# Bats-n-Gons.net
KiCad netlist of a schematic drawn in EAGLE
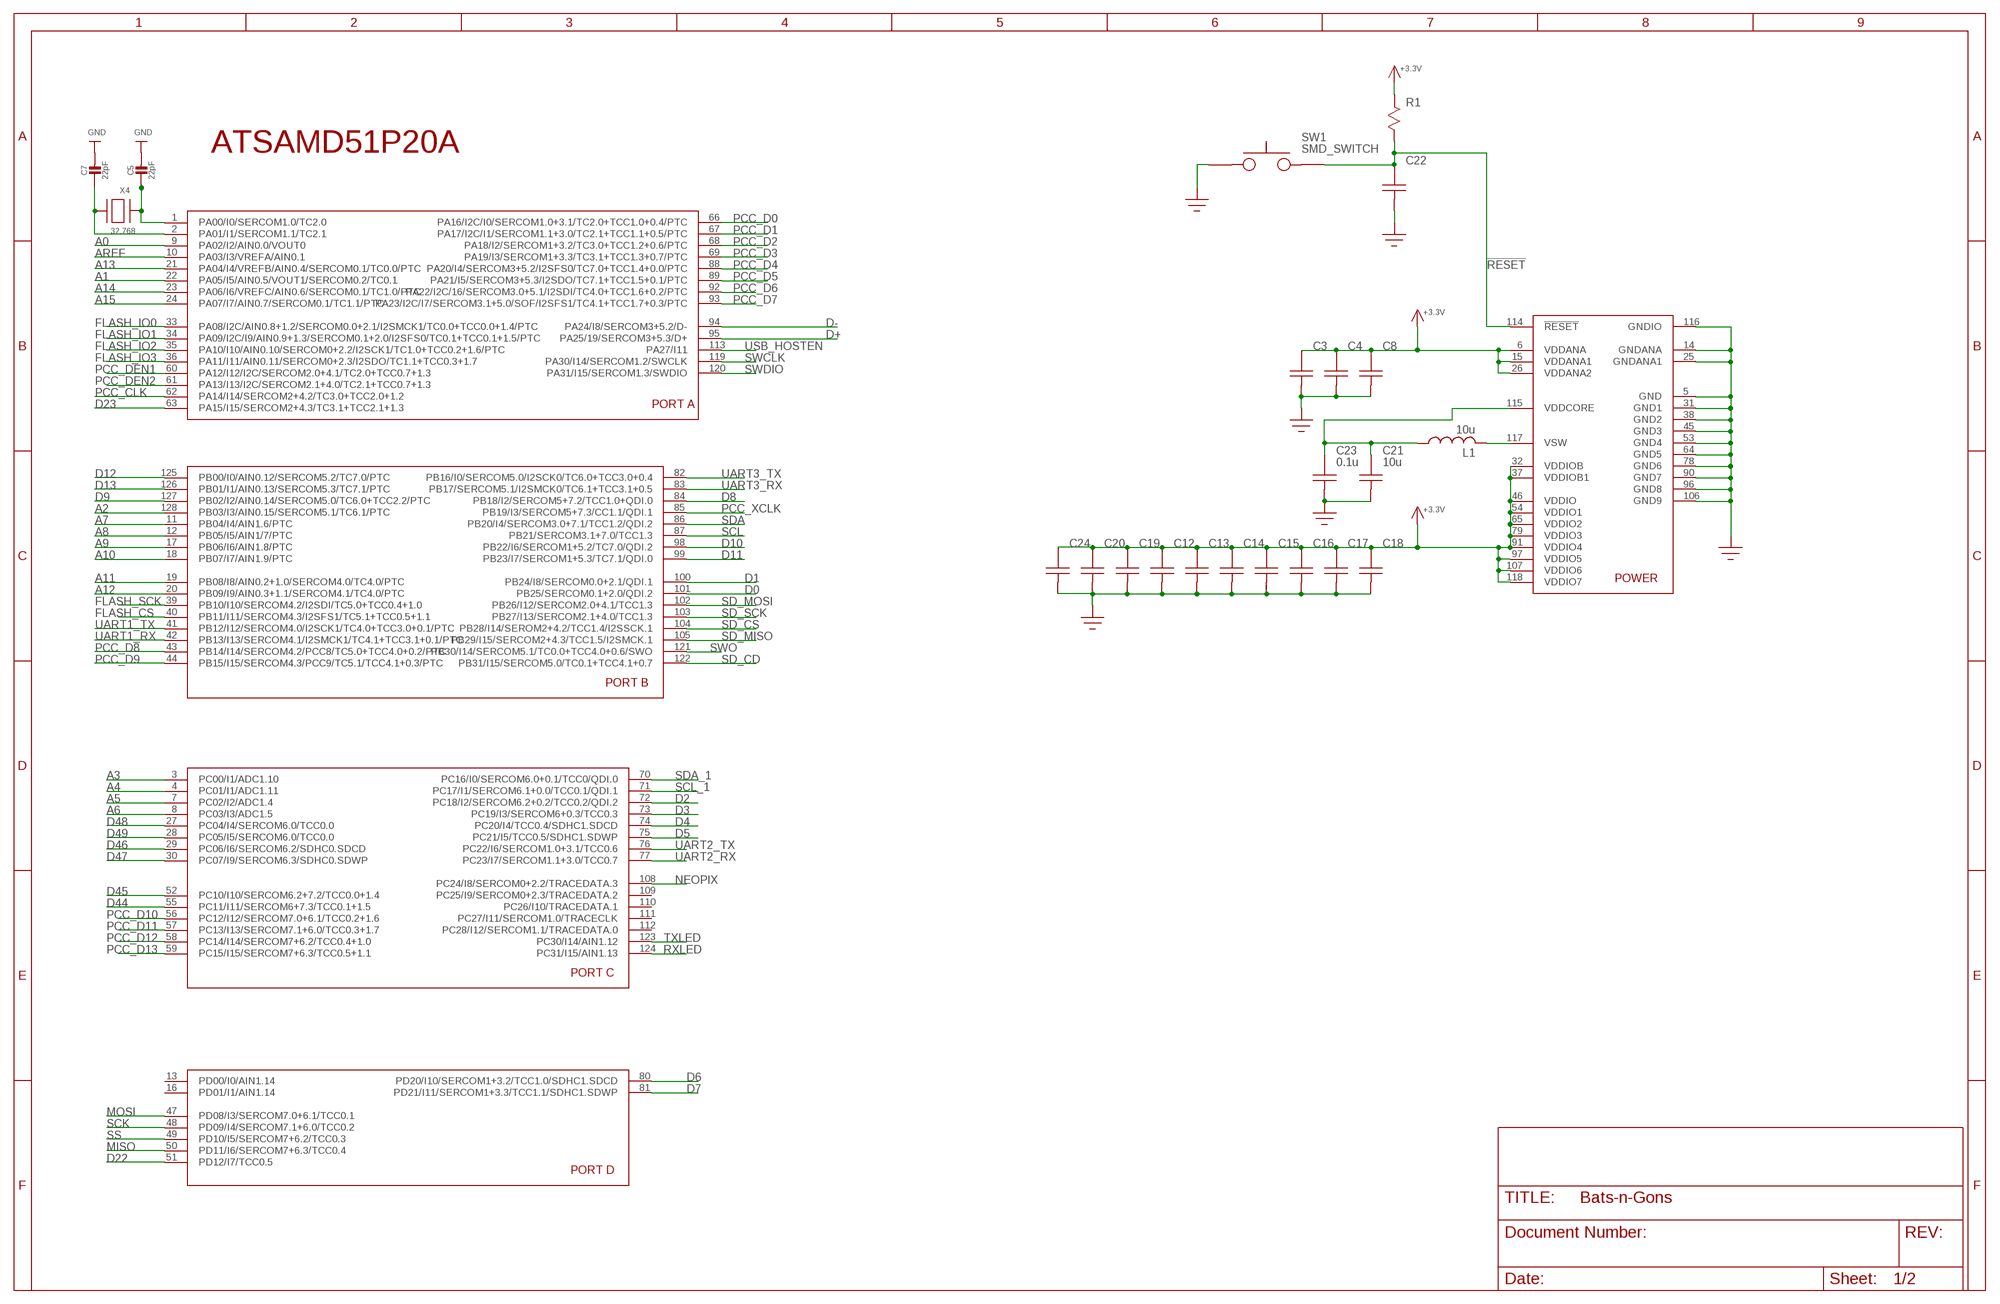
[diagram p0: schematic, sheet 1]
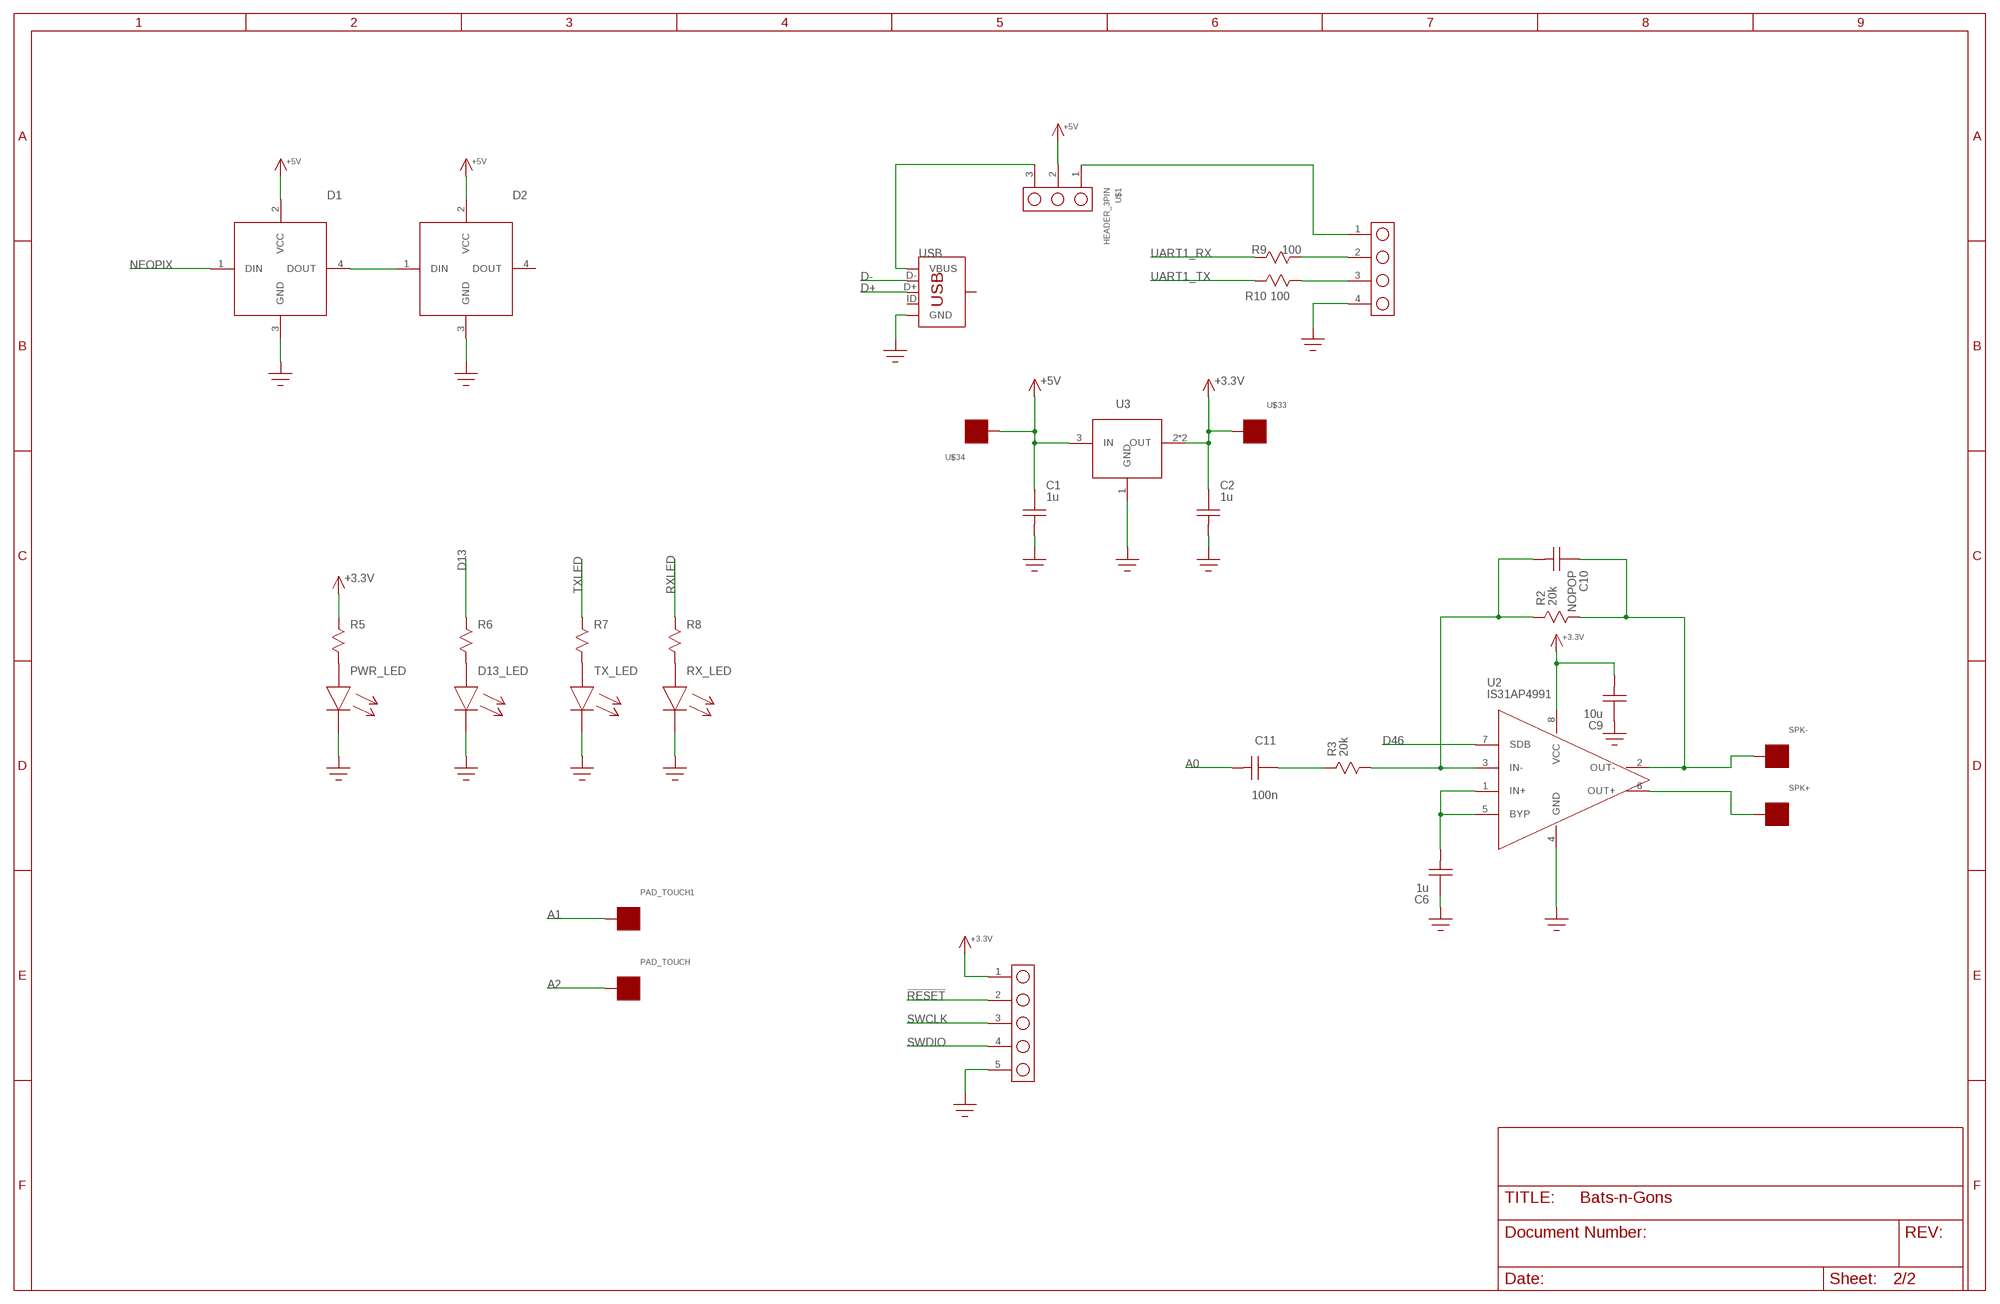
[diagram p1: schematic, sheet 2]

(export (version "E")
  (design (tool "Eeschema 10.0.6"))
  (components
    (comp (ref "C3")
      (value "C0603")
      (footprint "eagle-import:C0603")
      (libsource (lib "eagle-import") (part "C0603"))
    )
    (comp (ref "C4")
      (value "C0603")
      (footprint "eagle-import:C0603")
      (libsource (lib "eagle-import") (part "C0603"))
    )
    (comp (ref "C5")
      (value "22pF")
      (footprint "eagle-import:0603-NO")
      (libsource (lib "eagle-import") (part "CAP_CERAMIC0603_NO"))
    )
    (comp (ref "C7")
      (value "22pF")
      (footprint "eagle-import:0603-NO")
      (libsource (lib "eagle-import") (part "CAP_CERAMIC0603_NO"))
    )
    (comp (ref "C8")
      (value "C0603")
      (footprint "eagle-import:C0603")
      (libsource (lib "eagle-import") (part "C0603"))
    )
    (comp (ref "C12")
      (value "C0603")
      (footprint "eagle-import:C0603")
      (libsource (lib "eagle-import") (part "C0603"))
    )
    (comp (ref "C13")
      (value "C0603")
      (footprint "eagle-import:C0603")
      (libsource (lib "eagle-import") (part "C0603"))
    )
    (comp (ref "C14")
      (value "C0603")
      (footprint "eagle-import:C0603")
      (libsource (lib "eagle-import") (part "C0603"))
    )
    (comp (ref "C15")
      (value "C0603")
      (footprint "eagle-import:C0603")
      (libsource (lib "eagle-import") (part "C0603"))
    )
    (comp (ref "C16")
      (value "C0603")
      (footprint "eagle-import:C0603")
      (libsource (lib "eagle-import") (part "C0603"))
    )
    (comp (ref "C17")
      (value "C0603")
      (footprint "eagle-import:C0603")
      (libsource (lib "eagle-import") (part "C0603"))
    )
    (comp (ref "C18")
      (value "C0603")
      (footprint "eagle-import:C0603")
      (libsource (lib "eagle-import") (part "C0603"))
    )
    (comp (ref "C19")
      (value "C0603")
      (footprint "eagle-import:C0603")
      (libsource (lib "eagle-import") (part "C0603"))
    )
    (comp (ref "C20")
      (value "C0603")
      (footprint "eagle-import:C0603")
      (libsource (lib "eagle-import") (part "C0603"))
    )
    (comp (ref "C21")
      (value "10u")
      (footprint "eagle-import:C0603")
      (libsource (lib "eagle-import") (part "C0603"))
    )
    (comp (ref "C22")
      (value "C0603")
      (footprint "eagle-import:C0603")
      (libsource (lib "eagle-import") (part "C0603"))
    )
    (comp (ref "C23")
      (value "0.1u")
      (footprint "eagle-import:C0603")
      (libsource (lib "eagle-import") (part "C0603"))
    )
    (comp (ref "C24")
      (value "C0603")
      (footprint "eagle-import:C0603")
      (libsource (lib "eagle-import") (part "C0603"))
    )
    (comp (ref "L1")
      (value "10u")
      (footprint "eagle-import:L24X24")
      (libsource (lib "eagle-import") (part "INDUCTOR2424"))
    )
    (comp (ref "R1")
      (value "R0603")
      (footprint "eagle-import:R0603")
      (libsource (lib "eagle-import") (part "R0603"))
    )
    (comp (ref "SW1")
      (value "SMD_SWITCH")
      (footprint "eagle-import:SMD_SWITCH")
      (libsource (lib "eagle-import") (part "SMD_SWITCH"))
    )
    (comp (ref "U1")
      (value "SAMD51PXXA")
      (footprint "eagle-import:SQFP-S-14X14-128")
      (libsource (lib "eagle-import") (part "SAMD51PXXA"))
    )
    (comp (ref "X4")
      (value "32.768")
      (footprint "eagle-import:XTAL3215")
      (libsource (lib "eagle-import") (part "XTAL-3.2X1.5"))
    )
    (comp (ref "C1")
      (value "1u")
      (footprint "eagle-import:C0603")
      (libsource (lib "eagle-import") (part "yapo_C0603"))
    )
    (comp (ref "C2")
      (value "1u")
      (footprint "eagle-import:C0603")
      (libsource (lib "eagle-import") (part "yapo_C0603"))
    )
    (comp (ref "C6")
      (value "1u")
      (footprint "eagle-import:C0603")
      (libsource (lib "eagle-import") (part "C0603"))
    )
    (comp (ref "C9")
      (value "10u")
      (footprint "eagle-import:1206")
      (libsource (lib "eagle-import") (part "C1206"))
    )
    (comp (ref "C10")
      (value "NOPOP")
      (footprint "eagle-import:C0603")
      (libsource (lib "eagle-import") (part "C0603"))
    )
    (comp (ref "C11")
      (value "100n")
      (footprint "eagle-import:C0603")
      (libsource (lib "eagle-import") (part "C0603"))
    )
    (comp (ref "D1")
      (value "NEOPIXEL")
      (footprint "eagle-import:LED-RGB-THRU")
      (libsource (lib "eagle-import") (part "NEOPIXEL"))
    )
    (comp (ref "D2")
      (value "NEOPIXEL")
      (footprint "eagle-import:LED-RGB-THRU")
      (libsource (lib "eagle-import") (part "NEOPIXEL"))
    )
    (comp (ref "D13_LED")
      (value "LED_0603")
      (footprint "eagle-import:LED_0603")
      (libsource (lib "eagle-import") (part "LED_0603"))
    )
    (comp (ref "J1")
      (value "HEADER_4PIN")
      (footprint "eagle-import:HEADER_4PIN")
      (libsource (lib "eagle-import") (part "HEADER_4PIN"))
    )
    (comp (ref "J2")
      (value "HEADER_5PIN")
      (footprint "eagle-import:HEADER_5PIN")
      (libsource (lib "eagle-import") (part "HEADER_5PIN"))
    )
    (comp (ref "PAD_TOUCH")
      (value "PAD")
      (footprint "eagle-import:PAD-ROUND-100MIL-MASK")
      (libsource (lib "eagle-import") (part "PAD"))
    )
    (comp (ref "PAD_TOUCH1")
      (value "PAD")
      (footprint "eagle-import:PAD-ROUND-100MIL-MASK")
      (libsource (lib "eagle-import") (part "PAD"))
    )
    (comp (ref "PWR_LED")
      (value "LED_0603")
      (footprint "eagle-import:LED_0603")
      (libsource (lib "eagle-import") (part "LED_0603"))
    )
    (comp (ref "R2")
      (value "20k")
      (footprint "eagle-import:R0603")
      (libsource (lib "eagle-import") (part "R0603"))
    )
    (comp (ref "R3")
      (value "20k")
      (footprint "eagle-import:R0603")
      (libsource (lib "eagle-import") (part "R0603"))
    )
    (comp (ref "R5")
      (value "R0603")
      (footprint "eagle-import:R0603")
      (libsource (lib "eagle-import") (part "R0603"))
    )
    (comp (ref "R6")
      (value "R0603")
      (footprint "eagle-import:R0603")
      (libsource (lib "eagle-import") (part "R0603"))
    )
    (comp (ref "R7")
      (value "R0603")
      (footprint "eagle-import:R0603")
      (libsource (lib "eagle-import") (part "R0603"))
    )
    (comp (ref "R8")
      (value "R0603")
      (footprint "eagle-import:R0603")
      (libsource (lib "eagle-import") (part "R0603"))
    )
    (comp (ref "R9")
      (value "100")
      (footprint "eagle-import:R0603")
      (libsource (lib "eagle-import") (part "R0603"))
    )
    (comp (ref "R10")
      (value "100")
      (footprint "eagle-import:R0603")
      (libsource (lib "eagle-import") (part "R0603"))
    )
    (comp (ref "RX_LED")
      (value "LED_0603")
      (footprint "eagle-import:LED_0603")
      (libsource (lib "eagle-import") (part "LED_0603"))
    )
    (comp (ref "SPK+")
      (value "PAD100MIL")
      (footprint "eagle-import:PAD_100MIL")
      (libsource (lib "eagle-import") (part "PAD100MIL"))
    )
    (comp (ref "SPK-")
      (value "PAD100MIL")
      (footprint "eagle-import:PAD_100MIL")
      (libsource (lib "eagle-import") (part "PAD100MIL"))
    )
    (comp (ref "TX_LED")
      (value "LED_0603")
      (footprint "eagle-import:LED_0603")
      (libsource (lib "eagle-import") (part "LED_0603"))
    )
    (comp (ref "U$1")
      (value "HEADER_3PIN")
      (footprint "eagle-import:HEADER_3PIN")
      (libsource (lib "eagle-import") (part "HEADER_3PIN"))
    )
    (comp (ref "U$33")
      (value "PADROUND-50MIL")
      (footprint "eagle-import:PAD-ROUND-50MIL")
      (libsource (lib "eagle-import") (part "PADROUND-50MIL"))
    )
    (comp (ref "U$34")
      (value "PADROUND-50MIL")
      (footprint "eagle-import:PAD-ROUND-50MIL")
      (libsource (lib "eagle-import") (part "PADROUND-50MIL"))
    )
    (comp (ref "U2")
      (value "IS31AP4991")
      (footprint "eagle-import:SOIC8")
      (libsource (lib "eagle-import") (part "IS31AP4991SOIC"))
    )
    (comp (ref "U3")
      (value "AZ1117E")
      (footprint "eagle-import:SOT-223")
      (libsource (lib "eagle-import") (part "AZ1117E"))
    )
    (comp (ref "USB")
      (value "USB_MICRO_LEGS")
      (footprint "eagle-import:USB_MICRO_LEGS_2")
      (libsource (lib "eagle-import") (part "USB_MICRO_LEGS"))
    )
  )
  (nets
    (net (code "1") (name "+3.3V") (class "Default")
      (node (ref "C12") (pin "P$2") (pinfunction "P$2_P$2") (pintype "bidirectional"))
      (node (ref "C13") (pin "P$2") (pinfunction "P$2_P$2") (pintype "bidirectional"))
      (node (ref "C14") (pin "P$2") (pinfunction "P$2_P$2") (pintype "bidirectional"))
      (node (ref "C15") (pin "P$2") (pinfunction "P$2_P$2") (pintype "bidirectional"))
      (node (ref "C16") (pin "P$2") (pinfunction "P$2_P$2") (pintype "bidirectional"))
      (node (ref "C17") (pin "P$2") (pinfunction "P$2_P$2") (pintype "bidirectional"))
      (node (ref "C18") (pin "P$2") (pinfunction "P$2_P$2") (pintype "bidirectional"))
      (node (ref "C19") (pin "P$2") (pinfunction "P$2_P$2") (pintype "bidirectional"))
      (node (ref "C2") (pin "P$2") (pinfunction "P$2_P$2") (pintype "bidirectional"))
      (node (ref "C20") (pin "P$2") (pinfunction "P$2_P$2") (pintype "bidirectional"))
      (node (ref "C24") (pin "P$2") (pinfunction "P$2_P$2") (pintype "bidirectional"))
      (node (ref "C3") (pin "P$2") (pinfunction "P$2_P$2") (pintype "bidirectional"))
      (node (ref "C4") (pin "P$2") (pinfunction "P$2_P$2") (pintype "bidirectional"))
      (node (ref "C8") (pin "P$2") (pinfunction "P$2_P$2") (pintype "bidirectional"))
      (node (ref "C9") (pin "P$1") (pinfunction "P$1_P$1") (pintype "bidirectional"))
      (node (ref "J2") (pin "1") (pinfunction "1_1") (pintype "bidirectional"))
      (node (ref "R1") (pin "P$1") (pinfunction "P$3_P$1") (pintype "bidirectional"))
      (node (ref "R5") (pin "P$1") (pinfunction "P$3_P$1") (pintype "bidirectional"))
      (node (ref "U$33") (pin "P$1") (pinfunction "P$1_P$1") (pintype "bidirectional"))
      (node (ref "U1") (pin "107") (pinfunction "VDDIO6_107") (pintype "bidirectional"))
      (node (ref "U1") (pin "118") (pinfunction "VDDIO7_118") (pintype "bidirectional"))
      (node (ref "U1") (pin "15") (pinfunction "VDDANA1_15") (pintype "bidirectional"))
      (node (ref "U1") (pin "26") (pinfunction "VDDANA2_26") (pintype "bidirectional"))
      (node (ref "U1") (pin "32") (pinfunction "VDDIOB_32") (pintype "bidirectional"))
      (node (ref "U1") (pin "37") (pinfunction "VDDIOB1_37") (pintype "bidirectional"))
      (node (ref "U1") (pin "46") (pinfunction "VDDIO_46") (pintype "bidirectional"))
      (node (ref "U1") (pin "54") (pinfunction "VDDIO1_54") (pintype "bidirectional"))
      (node (ref "U1") (pin "6") (pinfunction "VDDANA_6") (pintype "bidirectional"))
      (node (ref "U1") (pin "65") (pinfunction "VDDIO2_65") (pintype "bidirectional"))
      (node (ref "U1") (pin "79") (pinfunction "VDDIO3_79") (pintype "bidirectional"))
      (node (ref "U1") (pin "91") (pinfunction "VDDIO4_91") (pintype "bidirectional"))
      (node (ref "U1") (pin "97") (pinfunction "VDDIO5_97") (pintype "bidirectional"))
      (node (ref "U2") (pin "8") (pinfunction "VCC_8") (pintype "bidirectional"))
      (node (ref "U3") (pin "2") (pinfunction "OUT_2") (pintype "bidirectional"))
      (node (ref "U3") (pin "4") (pinfunction "OUT_4") (pintype "bidirectional"))
    )
    (net (code "2") (name "+5V") (class "Default")
      (node (ref "C1") (pin "P$2") (pinfunction "P$2_P$2") (pintype "bidirectional"))
      (node (ref "D1") (pin "2") (pinfunction "VCC_2") (pintype "bidirectional"))
      (node (ref "D2") (pin "2") (pinfunction "VCC_2") (pintype "bidirectional"))
      (node (ref "U$1") (pin "2") (pinfunction "2_2") (pintype "bidirectional"))
      (node (ref "U$34") (pin "P$1") (pinfunction "P$1_P$1") (pintype "bidirectional"))
      (node (ref "U3") (pin "3") (pinfunction "IN_3") (pintype "bidirectional"))
    )
    (net (code "3") (name "A0") (class "Default")
      (node (ref "C11") (pin "P$1") (pinfunction "P$1_P$1") (pintype "bidirectional"))
      (node (ref "U1") (pin "9") (pinfunction "PA02/I2/AIN0.0/VOUT0_9") (pintype "bidirectional"))
    )
    (net (code "4") (name "A1") (class "Default")
      (node (ref "PAD_TOUCH1") (pin "P$1") (pinfunction "P$1_P$1") (pintype "bidirectional"))
      (node (ref "U1") (pin "22") (pinfunction "PA05/I5/AIN0.5/VOUT1/SERCOM0.2/TC0.1_22") (pintype "bidirectional"))
    )
    (net (code "5") (name "A2") (class "Default")
      (node (ref "PAD_TOUCH") (pin "P$1") (pinfunction "P$1_P$1") (pintype "bidirectional"))
      (node (ref "U1") (pin "128") (pinfunction "PB03/I3/AIN0.15/SERCOM5.1/TC6.1/PTC_128") (pintype "bidirectional"))
    )
    (net (code "6") (name "A3") (class "Default")
      (node (ref "U1") (pin "3") (pinfunction "PC00/I1/ADC1.10_3") (pintype "bidirectional"))
    )
    (net (code "7") (name "A4") (class "Default")
      (node (ref "U1") (pin "4") (pinfunction "PC01/I1/ADC1.11_4") (pintype "bidirectional"))
    )
    (net (code "8") (name "A5") (class "Default")
      (node (ref "U1") (pin "7") (pinfunction "PC02/I2/ADC1.4_7") (pintype "bidirectional"))
    )
    (net (code "9") (name "A6") (class "Default")
      (node (ref "U1") (pin "8") (pinfunction "PC03/I3/ADC1.5_8") (pintype "bidirectional"))
    )
    (net (code "10") (name "A7") (class "Default")
      (node (ref "U1") (pin "11") (pinfunction "PB04/I4/AIN1.6/PTC_11") (pintype "bidirectional"))
    )
    (net (code "11") (name "A8") (class "Default")
      (node (ref "U1") (pin "12") (pinfunction "PB05/I5/AIN1/7/PTC_12") (pintype "bidirectional"))
    )
    (net (code "12") (name "A9") (class "Default")
      (node (ref "U1") (pin "17") (pinfunction "PB06/I6/AIN1.8/PTC_17") (pintype "bidirectional"))
    )
    (net (code "13") (name "A10") (class "Default")
      (node (ref "U1") (pin "18") (pinfunction "PB07/I7/AIN1.9/PTC_18") (pintype "bidirectional"))
    )
    (net (code "14") (name "A11") (class "Default")
      (node (ref "U1") (pin "19") (pinfunction "PB08/I8/AIN0.2+1.0/SERCOM4.0/TC4.0/PTC_19") (pintype "bidirectional"))
    )
    (net (code "15") (name "A12") (class "Default")
      (node (ref "U1") (pin "20") (pinfunction "PB09/I9/AIN0.3+1.1/SERCOM4.1/TC4.0/PTC_20") (pintype "bidirectional"))
    )
    (net (code "16") (name "A13") (class "Default")
      (node (ref "U1") (pin "21") (pinfunction "PA04/I4/VREFB/AIN0.4/SERCOM0.1/TC0.0/PTC_21") (pintype "bidirectional"))
    )
    (net (code "17") (name "A14") (class "Default")
      (node (ref "U1") (pin "23") (pinfunction "PA06/I6/VREFC/AIN0.6/SERCOM0.1/TC1.0/PTC_23") (pintype "bidirectional"))
    )
    (net (code "18") (name "A15") (class "Default")
      (node (ref "U1") (pin "24") (pinfunction "PA07/I7/AIN0.7/SERCOM0.1/TC1.1/PTC_24") (pintype "bidirectional"))
    )
    (net (code "19") (name "AREF") (class "Default")
      (node (ref "U1") (pin "10") (pinfunction "PA03/I3/VREFA/AIN0.1_10") (pintype "bidirectional"))
    )
    (net (code "20") (name "D+") (class "Default")
      (node (ref "U1") (pin "95") (pinfunction "PA25/19/SERCOM3+5.3/D+_95") (pintype "bidirectional"))
      (node (ref "USB") (pin "D+") (pinfunction "D+_D+") (pintype "bidirectional"))
    )
    (net (code "21") (name "D-") (class "Default")
      (node (ref "U1") (pin "94") (pinfunction "PA24/I8/SERCOM3+5.2/D-_94") (pintype "bidirectional"))
      (node (ref "USB") (pin "D-") (pinfunction "D-_D-") (pintype "bidirectional"))
    )
    (net (code "22") (name "D0") (class "Default")
      (node (ref "U1") (pin "101") (pinfunction "PB25/SERCOM0.1+2.0/QDI.2_101") (pintype "bidirectional"))
    )
    (net (code "23") (name "D1") (class "Default")
      (node (ref "U1") (pin "100") (pinfunction "PB24/I8/SERCOM0.0+2.1/QDI.1_100") (pintype "bidirectional"))
    )
    (net (code "24") (name "D2") (class "Default")
      (node (ref "U1") (pin "72") (pinfunction "PC18/I2/SERCOM6.2+0.2/TCC0.2/QDI.2_72") (pintype "bidirectional"))
    )
    (net (code "25") (name "D3") (class "Default")
      (node (ref "U1") (pin "73") (pinfunction "PC19/I3/SERCOM6+0.3/TCC0.3_73") (pintype "bidirectional"))
    )
    (net (code "26") (name "D4") (class "Default")
      (node (ref "U1") (pin "74") (pinfunction "PC20/I4/TCC0.4/SDHC1.SDCD_74") (pintype "bidirectional"))
    )
    (net (code "27") (name "D5") (class "Default")
      (node (ref "U1") (pin "75") (pinfunction "PC21/I5/TCC0.5/SDHC1.SDWP_75") (pintype "bidirectional"))
    )
    (net (code "28") (name "D6") (class "Default")
      (node (ref "U1") (pin "80") (pinfunction "PD20/I10/SERCOM1+3.2/TCC1.0/SDHC1.SDCD_80") (pintype "bidirectional"))
    )
    (net (code "29") (name "D7") (class "Default")
      (node (ref "U1") (pin "81") (pinfunction "PD21/I11/SERCOM1+3.3/TCC1.1/SDHC1.SDWP_81") (pintype "bidirectional"))
    )
    (net (code "30") (name "D8") (class "Default")
      (node (ref "U1") (pin "84") (pinfunction "PB18/I2/SERCOM5+7.2/TCC1.0+QDI.0_84") (pintype "bidirectional"))
    )
    (net (code "31") (name "D9") (class "Default")
      (node (ref "U1") (pin "127") (pinfunction "PB02/I2/AIN0.14/SERCOM5.0/TC6.0+TCC2.2/PTC_127") (pintype "bidirectional"))
    )
    (net (code "32") (name "D10") (class "Default")
      (node (ref "U1") (pin "98") (pinfunction "PB22/I6/SERCOM1+5.2/TC7.0/QDI.2_98") (pintype "bidirectional"))
    )
    (net (code "33") (name "D11") (class "Default")
      (node (ref "U1") (pin "99") (pinfunction "PB23/I7/SERCOM1+5.3/TC7.1/QDI.0_99") (pintype "bidirectional"))
    )
    (net (code "34") (name "D12") (class "Default")
      (node (ref "U1") (pin "125") (pinfunction "PB00/I0/AIN0.12/SERCOM5.2/TC7.0/PTC_125") (pintype "bidirectional"))
    )
    (net (code "35") (name "D13") (class "Default")
      (node (ref "R6") (pin "P$1") (pinfunction "P$3_P$1") (pintype "bidirectional"))
      (node (ref "U1") (pin "126") (pinfunction "PB01/I1/AIN0.13/SERCOM5.3/TC7.1/PTC_126") (pintype "bidirectional"))
    )
    (net (code "36") (name "D22") (class "Default")
      (node (ref "U1") (pin "51") (pinfunction "PD12/I7/TCC0.5_51") (pintype "bidirectional"))
    )
    (net (code "37") (name "D23") (class "Default")
      (node (ref "U1") (pin "63") (pinfunction "PA15/I15/SERCOM2+4.3/TC3.1+TCC2.1+1.3_63") (pintype "bidirectional"))
    )
    (net (code "38") (name "D44") (class "Default")
      (node (ref "U1") (pin "55") (pinfunction "PC11/I11/SERCOM6+7.3/TCC0.1+1.5_55") (pintype "bidirectional"))
    )
    (net (code "39") (name "D45") (class "Default")
      (node (ref "U1") (pin "52") (pinfunction "PC10/I10/SERCOM6.2+7.2/TCC0.0+1.4_52") (pintype "bidirectional"))
    )
    (net (code "40") (name "D46") (class "Default")
      (node (ref "U1") (pin "29") (pinfunction "PC06/I6/SERCOM6.2/SDHC0.SDCD_29") (pintype "bidirectional"))
      (node (ref "U2") (pin "7") (pinfunction "SDB_7") (pintype "bidirectional"))
    )
    (net (code "41") (name "D47") (class "Default")
      (node (ref "U1") (pin "30") (pinfunction "PC07/I9/SERCOM6.3/SDHC0.SDWP_30") (pintype "bidirectional"))
    )
    (net (code "42") (name "D48") (class "Default")
      (node (ref "U1") (pin "27") (pinfunction "PC04/I4/SERCOM6.0/TCC0.0_27") (pintype "bidirectional"))
    )
    (net (code "43") (name "D49") (class "Default")
      (node (ref "U1") (pin "28") (pinfunction "PC05/I5/SERCOM6.0/TCC0.0_28") (pintype "bidirectional"))
    )
    (net (code "44") (name "FLASH_CS") (class "Default")
      (node (ref "U1") (pin "40") (pinfunction "PB11/I11/SERCOM4.3/I2SFS1/TC5.1+TCC0.5+1.1_40") (pintype "bidirectional"))
    )
    (net (code "45") (name "FLASH_IO0") (class "Default")
      (node (ref "U1") (pin "33") (pinfunction "PA08/I2C/AIN0.8+1.2/SERCOM0.0+2.1/I2SMCK1/TC0.0+TCC0.0+1.4/PTC_33") (pintype "bidirectional"))
    )
    (net (code "46") (name "FLASH_IO1") (class "Default")
      (node (ref "U1") (pin "34") (pinfunction "PA09/I2C/I9/AIN0.9+1.3/SERCOM0.1+2.0/I2SFS0/TC0.1+TCC0.1+1.5/PTC_34") (pintype "bidirectional"))
    )
    (net (code "47") (name "FLASH_IO2") (class "Default")
      (node (ref "U1") (pin "35") (pinfunction "PA10/I10/AIN0.10/SERCOM0+2.2/I2SCK1/TC1.0+TCC0.2+1.6/PTC_35") (pintype "bidirectional"))
    )
    (net (code "48") (name "FLASH_IO3") (class "Default")
      (node (ref "U1") (pin "36") (pinfunction "PA11/I11/AIN0.11/SERCOM0+2.3/I2SDO/TC1.1+TCC0.3+1.7_36") (pintype "bidirectional"))
    )
    (net (code "49") (name "FLASH_SCK") (class "Default")
      (node (ref "U1") (pin "39") (pinfunction "PB10/I10/SERCOM4.2/I2SDI/TC5.0+TCC0.4+1.0_39") (pintype "bidirectional"))
    )
    (net (code "50") (name "GND") (class "Default")
      (node (ref "C1") (pin "P$1") (pinfunction "P$1_P$1") (pintype "bidirectional"))
      (node (ref "C12") (pin "P$1") (pinfunction "P$1_P$1") (pintype "bidirectional"))
      (node (ref "C13") (pin "P$1") (pinfunction "P$1_P$1") (pintype "bidirectional"))
      (node (ref "C14") (pin "P$1") (pinfunction "P$1_P$1") (pintype "bidirectional"))
      (node (ref "C15") (pin "P$1") (pinfunction "P$1_P$1") (pintype "bidirectional"))
      (node (ref "C16") (pin "P$1") (pinfunction "P$1_P$1") (pintype "bidirectional"))
      (node (ref "C17") (pin "P$1") (pinfunction "P$1_P$1") (pintype "bidirectional"))
      (node (ref "C18") (pin "P$1") (pinfunction "P$1_P$1") (pintype "bidirectional"))
      (node (ref "C19") (pin "P$1") (pinfunction "P$1_P$1") (pintype "bidirectional"))
      (node (ref "C2") (pin "P$1") (pinfunction "P$1_P$1") (pintype "bidirectional"))
      (node (ref "C20") (pin "P$1") (pinfunction "P$1_P$1") (pintype "bidirectional"))
      (node (ref "C21") (pin "P$1") (pinfunction "P$1_P$1") (pintype "bidirectional"))
      (node (ref "C22") (pin "P$1") (pinfunction "P$1_P$1") (pintype "bidirectional"))
      (node (ref "C23") (pin "P$1") (pinfunction "P$1_P$1") (pintype "bidirectional"))
      (node (ref "C24") (pin "P$1") (pinfunction "P$1_P$1") (pintype "bidirectional"))
      (node (ref "C3") (pin "P$1") (pinfunction "P$1_P$1") (pintype "bidirectional"))
      (node (ref "C4") (pin "P$1") (pinfunction "P$1_P$1") (pintype "bidirectional"))
      (node (ref "C5") (pin "2") (pinfunction "2_2") (pintype "passive"))
      (node (ref "C6") (pin "P$2") (pinfunction "P$2_P$2") (pintype "bidirectional"))
      (node (ref "C7") (pin "2") (pinfunction "2_2") (pintype "passive"))
      (node (ref "C8") (pin "P$1") (pinfunction "P$1_P$1") (pintype "bidirectional"))
      (node (ref "C9") (pin "P$2") (pinfunction "P$2_P$2") (pintype "bidirectional"))
      (node (ref "D1") (pin "3") (pinfunction "GND_3") (pintype "bidirectional"))
      (node (ref "D13_LED") (pin "C") (pinfunction "C_C") (pintype "bidirectional"))
      (node (ref "D2") (pin "3") (pinfunction "GND_3") (pintype "bidirectional"))
      (node (ref "J1") (pin "4") (pinfunction "4_4") (pintype "bidirectional"))
      (node (ref "J2") (pin "5") (pinfunction "5_5") (pintype "bidirectional"))
      (node (ref "PWR_LED") (pin "C") (pinfunction "C_C") (pintype "bidirectional"))
      (node (ref "RX_LED") (pin "C") (pinfunction "C_C") (pintype "bidirectional"))
      (node (ref "SW1") (pin "P$1") (pinfunction "P$1_P$1") (pintype "bidirectional"))
      (node (ref "SW1") (pin "P$2") (pinfunction "P$1_P$2") (pintype "bidirectional"))
      (node (ref "TX_LED") (pin "C") (pinfunction "C_C") (pintype "bidirectional"))
      (node (ref "U1") (pin "106") (pinfunction "GND9_106") (pintype "bidirectional"))
      (node (ref "U1") (pin "116") (pinfunction "GNDIO_116") (pintype "bidirectional"))
      (node (ref "U1") (pin "14") (pinfunction "GNDANA_14") (pintype "bidirectional"))
      (node (ref "U1") (pin "25") (pinfunction "GNDANA1_25") (pintype "bidirectional"))
      (node (ref "U1") (pin "31") (pinfunction "GND1_31") (pintype "bidirectional"))
      (node (ref "U1") (pin "38") (pinfunction "GND2_38") (pintype "bidirectional"))
      (node (ref "U1") (pin "45") (pinfunction "GND3_45") (pintype "bidirectional"))
      (node (ref "U1") (pin "5") (pinfunction "GND_5") (pintype "bidirectional"))
      (node (ref "U1") (pin "53") (pinfunction "GND4_53") (pintype "bidirectional"))
      (node (ref "U1") (pin "64") (pinfunction "GND5_64") (pintype "bidirectional"))
      (node (ref "U1") (pin "78") (pinfunction "GND6_78") (pintype "bidirectional"))
      (node (ref "U1") (pin "90") (pinfunction "GND7_90") (pintype "bidirectional"))
      (node (ref "U1") (pin "96") (pinfunction "GND8_96") (pintype "bidirectional"))
      (node (ref "U2") (pin "4") (pinfunction "GND_4") (pintype "bidirectional"))
      (node (ref "U3") (pin "1") (pinfunction "GND_1") (pintype "bidirectional"))
      (node (ref "USB") (pin "GND") (pinfunction "GND_GND") (pintype "power_in"))
    )
    (net (code "51") (name "MISO") (class "Default")
      (node (ref "U1") (pin "50") (pinfunction "PD11/I6/SERCOM7+6.3/TCC0.4_50") (pintype "bidirectional"))
    )
    (net (code "52") (name "MOSI") (class "Default")
      (node (ref "U1") (pin "47") (pinfunction "PD08/I3/SERCOM7.0+6.1/TCC0.1_47") (pintype "bidirectional"))
    )
    (net (code "53") (name "NEOPIX") (class "Default")
      (node (ref "D1") (pin "1") (pinfunction "DIN_1") (pintype "bidirectional"))
      (node (ref "U1") (pin "108") (pinfunction "PC24/I8/SERCOM0+2.2/TRACEDATA.3_108") (pintype "bidirectional"))
    )
    (net (code "54") (name "Net-(D1-DOUT)") (class "Default")
      (node (ref "D1") (pin "4") (pinfunction "DOUT_4") (pintype "bidirectional"))
      (node (ref "D2") (pin "1") (pinfunction "DIN_1") (pintype "bidirectional"))
    )
    (net (code "55") (name "Net-(J1-Pad1)") (class "Default")
      (node (ref "J1") (pin "1") (pinfunction "1_1") (pintype "bidirectional"))
      (node (ref "U$1") (pin "1") (pinfunction "1_1") (pintype "bidirectional"))
    )
    (net (code "56") (name "Net-(R2-P$3)") (class "Default")
      (node (ref "C10") (pin "P$1") (pinfunction "P$1_P$1") (pintype "bidirectional"))
      (node (ref "R2") (pin "P$1") (pinfunction "P$3_P$1") (pintype "bidirectional"))
      (node (ref "R3") (pin "P$2") (pinfunction "P$4_P$2") (pintype "bidirectional"))
      (node (ref "U2") (pin "3") (pinfunction "IN-_3") (pintype "bidirectional"))
    )
    (net (code "57") (name "Net-(R2-P$4)") (class "Default")
      (node (ref "C10") (pin "P$2") (pinfunction "P$2_P$2") (pintype "bidirectional"))
      (node (ref "R2") (pin "P$2") (pinfunction "P$4_P$2") (pintype "bidirectional"))
      (node (ref "SPK-") (pin "P$1") (pinfunction "P$1_P$1") (pintype "bidirectional"))
      (node (ref "U2") (pin "2") (pinfunction "OUT-_2") (pintype "bidirectional"))
    )
    (net (code "58") (name "Net-(R3-P$3)") (class "Default")
      (node (ref "C11") (pin "P$2") (pinfunction "P$2_P$2") (pintype "bidirectional"))
      (node (ref "R3") (pin "P$1") (pinfunction "P$3_P$1") (pintype "bidirectional"))
    )
    (net (code "59") (name "Net-(R5-P$4)") (class "Default")
      (node (ref "PWR_LED") (pin "A") (pinfunction "A_A") (pintype "bidirectional"))
      (node (ref "R5") (pin "P$2") (pinfunction "P$4_P$2") (pintype "bidirectional"))
    )
    (net (code "60") (name "Net-(R6-P$4)") (class "Default")
      (node (ref "D13_LED") (pin "A") (pinfunction "A_A") (pintype "bidirectional"))
      (node (ref "R6") (pin "P$2") (pinfunction "P$4_P$2") (pintype "bidirectional"))
    )
    (net (code "61") (name "Net-(R7-P$4)") (class "Default")
      (node (ref "R7") (pin "P$2") (pinfunction "P$4_P$2") (pintype "bidirectional"))
      (node (ref "TX_LED") (pin "A") (pinfunction "A_A") (pintype "bidirectional"))
    )
    (net (code "62") (name "Net-(R8-P$4)") (class "Default")
      (node (ref "R8") (pin "P$2") (pinfunction "P$4_P$2") (pintype "bidirectional"))
      (node (ref "RX_LED") (pin "A") (pinfunction "A_A") (pintype "bidirectional"))
    )
    (net (code "63") (name "Net-(R9-P$4)") (class "Default")
      (node (ref "J1") (pin "2") (pinfunction "2_2") (pintype "bidirectional"))
      (node (ref "R9") (pin "P$2") (pinfunction "P$4_P$2") (pintype "bidirectional"))
    )
    (net (code "64") (name "Net-(R10-P$4)") (class "Default")
      (node (ref "J1") (pin "3") (pinfunction "3_3") (pintype "bidirectional"))
      (node (ref "R10") (pin "P$2") (pinfunction "P$4_P$2") (pintype "bidirectional"))
    )
    (net (code "65") (name "Net-(U$1-Pad3)") (class "Default")
      (node (ref "U$1") (pin "3") (pinfunction "3_3") (pintype "bidirectional"))
      (node (ref "USB") (pin "VBUS") (pinfunction "VBUS_VBUS") (pintype "power_in"))
    )
    (net (code "66") (name "Net-(U1A-PA00{slash}I0{slash}SERCOM1.0{slash}TC2.0)") (class "Default")
      (node (ref "C5") (pin "1") (pinfunction "1_1") (pintype "passive"))
      (node (ref "U1") (pin "1") (pinfunction "PA00/I0/SERCOM1.0/TC2.0_1") (pintype "bidirectional"))
      (node (ref "X4") (pin "P$1") (pinfunction "P$1_P$1") (pintype "bidirectional"))
    )
    (net (code "67") (name "Net-(U1A-PA01{slash}I1{slash}SERCOM1.1{slash}TC2.1)") (class "Default")
      (node (ref "C7") (pin "1") (pinfunction "1_1") (pintype "passive"))
      (node (ref "U1") (pin "2") (pinfunction "PA01/I1/SERCOM1.1/TC2.1_2") (pintype "bidirectional"))
      (node (ref "X4") (pin "P$2") (pinfunction "P$2_P$2") (pintype "bidirectional"))
    )
    (net (code "68") (name "Net-(U1E-VDDCORE)") (class "Default")
      (node (ref "C21") (pin "P$2") (pinfunction "P$2_P$2") (pintype "bidirectional"))
      (node (ref "C23") (pin "P$2") (pinfunction "P$2_P$2") (pintype "bidirectional"))
      (node (ref "L1") (pin "1") (pinfunction "1_1") (pintype "passive"))
      (node (ref "U1") (pin "115") (pinfunction "VDDCORE_115") (pintype "bidirectional"))
    )
    (net (code "69") (name "Net-(U1E-VSW)") (class "Default")
      (node (ref "L1") (pin "2") (pinfunction "2_2") (pintype "passive"))
      (node (ref "U1") (pin "117") (pinfunction "VSW_117") (pintype "bidirectional"))
    )
    (net (code "70") (name "Net-(U2-BYP)") (class "Default")
      (node (ref "C6") (pin "P$1") (pinfunction "P$1_P$1") (pintype "bidirectional"))
      (node (ref "U2") (pin "1") (pinfunction "IN+_1") (pintype "bidirectional"))
      (node (ref "U2") (pin "5") (pinfunction "BYP_5") (pintype "bidirectional"))
    )
    (net (code "71") (name "Net-(U2-OUT+)") (class "Default")
      (node (ref "SPK+") (pin "P$1") (pinfunction "P$1_P$1") (pintype "bidirectional"))
      (node (ref "U2") (pin "6") (pinfunction "OUT+_6") (pintype "bidirectional"))
    )
    (net (code "72") (name "PCC_CLK") (class "Default")
      (node (ref "U1") (pin "62") (pinfunction "PA14/I14/SERCOM2+4.2/TC3.0+TCC2.0+1.2_62") (pintype "bidirectional"))
    )
    (net (code "73") (name "PCC_D0") (class "Default")
      (node (ref "U1") (pin "66") (pinfunction "PA16/I2C/I0/SERCOM1.0+3.1/TC2.0+TCC1.0+0.4/PTC_66") (pintype "bidirectional"))
    )
    (net (code "74") (name "PCC_D1") (class "Default")
      (node (ref "U1") (pin "67") (pinfunction "PA17/I2C/I1/SERCOM1.1+3.0/TC2.1+TCC1.1+0.5/PTC_67") (pintype "bidirectional"))
    )
    (net (code "75") (name "PCC_D2") (class "Default")
      (node (ref "U1") (pin "68") (pinfunction "PA18/I2/SERCOM1+3.2/TC3.0+TCC1.2+0.6/PTC_68") (pintype "bidirectional"))
    )
    (net (code "76") (name "PCC_D3") (class "Default")
      (node (ref "U1") (pin "69") (pinfunction "PA19/I3/SERCOM1+3.3/TC3.1+TCC1.3+0.7/PTC_69") (pintype "bidirectional"))
    )
    (net (code "77") (name "PCC_D4") (class "Default")
      (node (ref "U1") (pin "88") (pinfunction "PA20/I4/SERCOM3+5.2/I2SFS0/TC7.0+TCC1.4+0.0/PTC_88") (pintype "bidirectional"))
    )
    (net (code "78") (name "PCC_D5") (class "Default")
      (node (ref "U1") (pin "89") (pinfunction "PA21/I5/SERCOM3+5.3/I2SDO/TC7.1+TCC1.5+0.1/PTC_89") (pintype "bidirectional"))
    )
    (net (code "79") (name "PCC_D6") (class "Default")
      (node (ref "U1") (pin "92") (pinfunction "PA22/I2C/16/SERCOM3.0+5.1/I2SDI/TC4.0+TCC1.6+0.2/PTC_92") (pintype "bidirectional"))
    )
    (net (code "80") (name "PCC_D7") (class "Default")
      (node (ref "U1") (pin "93") (pinfunction "PA23/I2C/I7/SERCOM3.1+5.0/SOF/I2SFS1/TC4.1+TCC1.7+0.3/PTC_93") (pintype "bidirectional"))
    )
    (net (code "81") (name "PCC_D8") (class "Default")
      (node (ref "U1") (pin "43") (pinfunction "PB14/I14/SERCOM4.2/PCC8/TC5.0+TCC4.0+0.2/PTC_43") (pintype "bidirectional"))
    )
    (net (code "82") (name "PCC_D9") (class "Default")
      (node (ref "U1") (pin "44") (pinfunction "PB15/I15/SERCOM4.3/PCC9/TC5.1/TCC4.1+0.3/PTC_44") (pintype "bidirectional"))
    )
    (net (code "83") (name "PCC_D10") (class "Default")
      (node (ref "U1") (pin "56") (pinfunction "PC12/I12/SERCOM7.0+6.1/TCC0.2+1.6_56") (pintype "bidirectional"))
    )
    (net (code "84") (name "PCC_D11") (class "Default")
      (node (ref "U1") (pin "57") (pinfunction "PC13/I13/SERCOM7.1+6.0/TCC0.3+1.7_57") (pintype "bidirectional"))
    )
    (net (code "85") (name "PCC_D12") (class "Default")
      (node (ref "U1") (pin "58") (pinfunction "PC14/I14/SERCOM7+6.2/TCC0.4+1.0_58") (pintype "bidirectional"))
    )
    (net (code "86") (name "PCC_D13") (class "Default")
      (node (ref "U1") (pin "59") (pinfunction "PC15/I15/SERCOM7+6.3/TCC0.5+1.1_59") (pintype "bidirectional"))
    )
    (net (code "87") (name "PCC_DEN1") (class "Default")
      (node (ref "U1") (pin "60") (pinfunction "PA12/I12/I2C/SERCOM2.0+4.1/TC2.0+TCC0.7+1.3_60") (pintype "bidirectional"))
    )
    (net (code "88") (name "PCC_DEN2") (class "Default")
      (node (ref "U1") (pin "61") (pinfunction "PA13/I13/I2C/SERCOM2.1+4.0/TC2.1+TCC0.7+1.3_61") (pintype "bidirectional"))
    )
    (net (code "89") (name "PCC_XCLK") (class "Default")
      (node (ref "U1") (pin "85") (pinfunction "PB19/I3/SERCOM5+7.3/CC1.1/QDI.1_85") (pintype "bidirectional"))
    )
    (net (code "90") (name "RXLED") (class "Default")
      (node (ref "R8") (pin "P$1") (pinfunction "P$3_P$1") (pintype "bidirectional"))
      (node (ref "U1") (pin "124") (pinfunction "PC31/I15/AIN1.13_124") (pintype "bidirectional"))
    )
    (net (code "91") (name "SCK") (class "Default")
      (node (ref "U1") (pin "48") (pinfunction "PD09/I4/SERCOM7.1+6.0/TCC0.2_48") (pintype "bidirectional"))
    )
    (net (code "92") (name "SCL") (class "Default")
      (node (ref "U1") (pin "87") (pinfunction "PB21/SERCOM3.1+7.0/TCC1.3_87") (pintype "bidirectional"))
    )
    (net (code "93") (name "SCL_1") (class "Default")
      (node (ref "U1") (pin "71") (pinfunction "PC17/I1/SERCOM6.1+0.0/TCC0.1/QDI.1_71") (pintype "bidirectional"))
    )
    (net (code "94") (name "SDA") (class "Default")
      (node (ref "U1") (pin "86") (pinfunction "PB20/I4/SERCOM3.0+7.1/TCC1.2/QDI.2_86") (pintype "bidirectional"))
    )
    (net (code "95") (name "SDA_1") (class "Default")
      (node (ref "U1") (pin "70") (pinfunction "PC16/I0/SERCOM6.0+0.1/TCC0/QDI.0_70") (pintype "bidirectional"))
    )
    (net (code "96") (name "SD_CD") (class "Default")
      (node (ref "U1") (pin "122") (pinfunction "PB31/I15/SERCOM5.0/TC0.1+TCC4.1+0.7_122") (pintype "bidirectional"))
    )
    (net (code "97") (name "SD_CS") (class "Default")
      (node (ref "U1") (pin "104") (pinfunction "PB28/I14/SEROM2+4.2/TCC1.4/I2SSCK.1_104") (pintype "bidirectional"))
    )
    (net (code "98") (name "SD_MISO") (class "Default")
      (node (ref "U1") (pin "105") (pinfunction "PB29/I15/SERCOM2+4.3/TCC1.5/I2SMCK.1_105") (pintype "bidirectional"))
    )
    (net (code "99") (name "SD_MOSI") (class "Default")
      (node (ref "U1") (pin "102") (pinfunction "PB26/I12/SERCOM2.0+4.1/TCC1.3_102") (pintype "bidirectional"))
    )
    (net (code "100") (name "SD_SCK") (class "Default")
      (node (ref "U1") (pin "103") (pinfunction "PB27/I13/SERCOM2.1+4.0/TCC1.3_103") (pintype "bidirectional"))
    )
    (net (code "101") (name "SS") (class "Default")
      (node (ref "U1") (pin "49") (pinfunction "PD10/I5/SERCOM7+6.2/TCC0.3_49") (pintype "bidirectional"))
    )
    (net (code "102") (name "SWCLK") (class "Default")
      (node (ref "J2") (pin "3") (pinfunction "3_3") (pintype "bidirectional"))
      (node (ref "U1") (pin "119") (pinfunction "PA30/I14/SERCOM1.2/SWCLK_119") (pintype "bidirectional"))
    )
    (net (code "103") (name "SWDIO") (class "Default")
      (node (ref "J2") (pin "4") (pinfunction "4_4") (pintype "bidirectional"))
      (node (ref "U1") (pin "120") (pinfunction "PA31/I15/SERCOM1.3/SWDIO_120") (pintype "bidirectional"))
    )
    (net (code "104") (name "SWO") (class "Default")
      (node (ref "U1") (pin "121") (pinfunction "PB30/I14/SERCOM5.1/TC0.0+TCC4.0+0.6/SWO_121") (pintype "bidirectional"))
    )
    (net (code "105") (name "TXLED") (class "Default")
      (node (ref "R7") (pin "P$1") (pinfunction "P$3_P$1") (pintype "bidirectional"))
      (node (ref "U1") (pin "123") (pinfunction "PC30/I14/AIN1.12_123") (pintype "bidirectional"))
    )
    (net (code "106") (name "UART1_RX") (class "Default")
      (node (ref "R9") (pin "P$1") (pinfunction "P$3_P$1") (pintype "bidirectional"))
      (node (ref "U1") (pin "42") (pinfunction "PB13/I13/SERCOM4.1/I2SMCK1/TC4.1+TCC3.1+0.1/PTC_42") (pintype "bidirectional"))
    )
    (net (code "107") (name "UART1_TX") (class "Default")
      (node (ref "R10") (pin "P$1") (pinfunction "P$3_P$1") (pintype "bidirectional"))
      (node (ref "U1") (pin "41") (pinfunction "PB12/I12/SERCOM4.0/I2SCK1/TC4.0+TCC3.0+0.1/PTC_41") (pintype "bidirectional"))
    )
    (net (code "108") (name "UART2_RX") (class "Default")
      (node (ref "U1") (pin "77") (pinfunction "PC23/I7/SERCOM1.1+3.0/TCC0.7_77") (pintype "bidirectional"))
    )
    (net (code "109") (name "UART2_TX") (class "Default")
      (node (ref "U1") (pin "76") (pinfunction "PC22/I6/SERCOM1.0+3.1/TCC0.6_76") (pintype "bidirectional"))
    )
    (net (code "110") (name "UART3_RX") (class "Default")
      (node (ref "U1") (pin "83") (pinfunction "PB17/SERCOM5.1/I2SMCK0/TC6.1+TCC3.1+0.5_83") (pintype "bidirectional"))
    )
    (net (code "111") (name "UART3_TX") (class "Default")
      (node (ref "U1") (pin "82") (pinfunction "PB16/I0/SERCOM5.0/I2SCK0/TC6.0+TCC3.0+0.4_82") (pintype "bidirectional"))
    )
    (net (code "112") (name "USB_HOSTEN") (class "Default")
      (node (ref "U1") (pin "113") (pinfunction "PA27/I11_113") (pintype "bidirectional"))
    )
    (net (code "113") (name "unconnected-(D2-DOUT-Pad4)") (class "Default")
      (node (ref "D2") (pin "4") (pinfunction "DOUT_4") (pintype "bidirectional"))
    )
    (net (code "114") (name "unconnected-(U1C-PC25{slash}I9{slash}SERCOM0+2.3{slash}TRACEDATA.2-Pad109)") (class "Default")
      (node (ref "U1") (pin "109") (pinfunction "PC25/I9/SERCOM0+2.3/TRACEDATA.2_109") (pintype "bidirectional"))
    )
    (net (code "115") (name "unconnected-(U1C-PC26{slash}I10{slash}TRACEDATA.1-Pad110)") (class "Default")
      (node (ref "U1") (pin "110") (pinfunction "PC26/I10/TRACEDATA.1_110") (pintype "bidirectional"))
    )
    (net (code "116") (name "unconnected-(U1C-PC27{slash}I11{slash}SERCOM1.0{slash}TRACECLK-Pad111)") (class "Default")
      (node (ref "U1") (pin "111") (pinfunction "PC27/I11/SERCOM1.0/TRACECLK_111") (pintype "bidirectional"))
    )
    (net (code "117") (name "unconnected-(U1C-PC28{slash}I12{slash}SERCOM1.1{slash}TRACEDATA.0-Pad112)") (class "Default")
      (node (ref "U1") (pin "112") (pinfunction "PC28/I12/SERCOM1.1/TRACEDATA.0_112") (pintype "bidirectional"))
    )
    (net (code "118") (name "unconnected-(U1D-PD00{slash}I0{slash}AIN1.14-Pad13)") (class "Default")
      (node (ref "U1") (pin "13") (pinfunction "PD00/I0/AIN1.14_13") (pintype "bidirectional"))
    )
    (net (code "119") (name "unconnected-(U1D-PD01{slash}I1{slash}AIN1.14-Pad16)") (class "Default")
      (node (ref "U1") (pin "16") (pinfunction "PD01/I1/AIN1.14_16") (pintype "bidirectional"))
    )
    (net (code "120") (name "unconnected-(USB-PadID)") (class "Default")
      (node (ref "USB") (pin "ID") (pinfunction "ID_ID") (pintype "bidirectional"))
    )
    (net (code "121") (name "unconnected-(USB-SHIELD-PadP$4)") (class "Default")
      (node (ref "USB") (pin "P$4") (pinfunction "SHIELD_P$4") (pintype "bidirectional"))
    )
    (net (code "122") (name "~{RESET}") (class "Default")
      (node (ref "C22") (pin "P$2") (pinfunction "P$2_P$2") (pintype "bidirectional"))
      (node (ref "J2") (pin "2") (pinfunction "2_2") (pintype "bidirectional"))
      (node (ref "R1") (pin "P$2") (pinfunction "P$4_P$2") (pintype "bidirectional"))
      (node (ref "SW1") (pin "P$3") (pinfunction "P$2_P$3") (pintype "bidirectional"))
      (node (ref "SW1") (pin "P$4") (pinfunction "P$2_P$4") (pintype "bidirectional"))
      (node (ref "U1") (pin "114") (pinfunction "~{RESET}_114") (pintype "bidirectional"))
    )
  )
)
